# Sheet1.net
KiCad netlist of a schematic drawn in Altium Designer
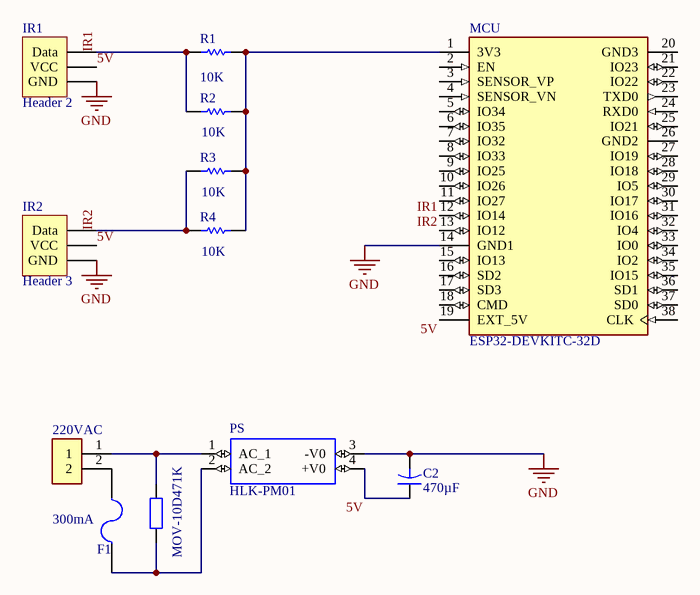
[diagram p0: Sheet1.SchDoc]

(export (version "E")
  (design (tool "Eeschema 10.0.6"))
  (components
    (comp (ref "220VAC")
      (value "282837-2")
      (footprint "TE_282837-2")
      (description "Connector Terminal Blocks Receptacle 2 Position 5.08mm Solder Straight Thru-Hole 13.5A/Contact")
      (fields (field (name "MF") "TE Connectivity") (field (name "DIGI-KEY_PART_NUMBER") "A113320-ND"))
      (libsource (lib "282837-2") (part "282837-2"))
    )
    (comp (ref "C2")
      (value "470µF")
      (footprint "CAPR5-4X5")
      (description "Capacitor")
      (fields (field (name "Comment") "Cap2") (field (name "PUBLISHER") "Altium Limited"))
      (libsource (lib "Miscellaneous Devices") (part "Cap2"))
    )
    (comp (ref "F1")
      (value "300mA")
      (footprint "PIN-W2/E2.8")
      (description "Fuse")
      (fields (field (name "PUBLISHER") "Altium Limited"))
      (libsource (lib "Miscellaneous Devices") (part "Fuse 2"))
    )
    (comp (ref "IR1")
      (value "Header 2")
      (footprint "HDR1X3")
      (description "Header, 3-Pin")
      (fields (field (name "PUBLISHER") "Altium Limited"))
      (libsource (lib "Miscellaneous Connectors") (part "Header 3"))
    )
    (comp (ref "IR2")
      (value "Header 3")
      (footprint "HDR1X3")
      (description "Header, 3-Pin")
      (fields (field (name "PUBLISHER") "Altium Limited"))
      (libsource (lib "Miscellaneous Connectors") (part "Header 3"))
    )
    (comp (ref "MCU")
      (value "ESP32-DEVKITC-32D")
      (footprint "MODULE_ESP32-DEVKITC-32D")
      (fields (field (name "MF") "Espressif Systems"))
      (libsource (lib "ESP32-DEVKITC-32D") (part "ESP32-DEVKITC-32D"))
    )
    (comp (ref "PS")
      (value "HLK-PM01")
      (footprint "HLKPM01")
      (fields (field (name "MF") "Hi-link") (field (name "MP") "hlk-pm01"))
      (libsource (lib "HLK-PM01") (part "HLK-PM01"))
    )
    (comp (ref "R1")
      (value "10K")
      (footprint "AXIAL-0.3")
      (description "Resistor")
      (fields (field (name "PUBLISHER") "Altium Limited"))
      (libsource (lib "Miscellaneous Devices") (part "Res1"))
    )
    (comp (ref "R2")
      (value "10K")
      (footprint "AXIAL-0.3")
      (description "Resistor")
      (fields (field (name "PUBLISHER") "Altium Limited"))
      (libsource (lib "Miscellaneous Devices") (part "Res1"))
    )
    (comp (ref "R3")
      (value "10K")
      (footprint "AXIAL-0.3")
      (description "Resistor")
      (fields (field (name "PUBLISHER") "Altium Limited"))
      (libsource (lib "Miscellaneous Devices") (part "Res1"))
    )
    (comp (ref "R4")
      (value "10K")
      (footprint "AXIAL-0.3")
      (description "Resistor")
      (fields (field (name "PUBLISHER") "Altium Limited"))
      (libsource (lib "Miscellaneous Devices") (part "Res1"))
    )
    (comp (ref "VAR1")
      (value "MOV-10D471K")
      (footprint "AXIAL-0.4")
      (fields (field (name "PUBLISHER") "Altium Limited"))
      (libsource (lib "Miscellaneous Devices") (part "Res2"))
    )
  )
  (nets
    (net (code "1") (name "/5V") (class "Default")
      (node (ref "C2") (pin "1") (pinfunction "1_1") (pintype "passive"))
      (node (ref "IR1") (pin "2") (pinfunction "VCC_2") (pintype "passive"))
      (node (ref "IR2") (pin "2") (pinfunction "VCC_2") (pintype "passive"))
      (node (ref "MCU") (pin "19") (pinfunction "EXT_5V_19") (pintype "power_in"))
      (node (ref "PS") (pin "4") (pinfunction "+V0_4") (pintype "bidirectional"))
    )
    (net (code "2") (name "/IR1") (class "Default")
      (node (ref "IR1") (pin "3") (pinfunction "Data_3") (pintype "passive"))
      (node (ref "MCU") (pin "12") (pinfunction "IO14_12") (pintype "bidirectional"))
      (node (ref "R1") (pin "2") (pinfunction "2_2") (pintype "passive"))
      (node (ref "R2") (pin "2") (pinfunction "2_2") (pintype "passive"))
    )
    (net (code "3") (name "/IR2") (class "Default")
      (node (ref "IR2") (pin "3") (pinfunction "Data_3") (pintype "passive"))
      (node (ref "MCU") (pin "13") (pinfunction "IO12_13") (pintype "bidirectional"))
      (node (ref "R3") (pin "2") (pinfunction "2_2") (pintype "passive"))
      (node (ref "R4") (pin "2") (pinfunction "2_2") (pintype "passive"))
    )
    (net (code "4") (name "GND") (class "Default")
      (node (ref "C2") (pin "2") (pinfunction "2_2") (pintype "passive"))
      (node (ref "IR1") (pin "1") (pinfunction "GND_1") (pintype "passive"))
      (node (ref "IR2") (pin "1") (pinfunction "GND_1") (pintype "passive"))
      (node (ref "MCU") (pin "14") (pinfunction "GND1_14") (pintype "power_in"))
      (node (ref "PS") (pin "3") (pinfunction "-V0_3") (pintype "bidirectional"))
    )
    (net (code "5") (name "Net-(220VAC-Pad2)") (class "Default")
      (node (ref "220VAC") (pin "2") (pinfunction "2_2") (pintype "passive"))
      (node (ref "F1") (pin "2") (pinfunction "2_2") (pintype "passive"))
    )
    (net (code "6") (name "Net-(MCU-3V3)") (class "Default")
      (node (ref "MCU") (pin "1") (pinfunction "3V3_1") (pintype "power_in"))
      (node (ref "R1") (pin "1") (pinfunction "1_1") (pintype "passive"))
      (node (ref "R2") (pin "1") (pinfunction "1_1") (pintype "passive"))
      (node (ref "R3") (pin "1") (pinfunction "1_1") (pintype "passive"))
      (node (ref "R4") (pin "1") (pinfunction "1_1") (pintype "passive"))
    )
    (net (code "7") (name "Net-(PS-AC_1)") (class "Default")
      (node (ref "220VAC") (pin "1") (pinfunction "1_1") (pintype "passive"))
      (node (ref "PS") (pin "1") (pinfunction "AC_1_1") (pintype "bidirectional"))
      (node (ref "VAR1") (pin "2") (pinfunction "2_2") (pintype "passive"))
    )
    (net (code "8") (name "Net-(PS-AC_2)") (class "Default")
      (node (ref "F1") (pin "1") (pinfunction "1_1") (pintype "passive"))
      (node (ref "PS") (pin "2") (pinfunction "AC_2_2") (pintype "bidirectional"))
      (node (ref "VAR1") (pin "1") (pinfunction "1_1") (pintype "passive"))
    )
    (net (code "9") (name "unconnected-(MCU-CLK-Pad38)") (class "Default")
      (node (ref "MCU") (pin "38") (pinfunction "CLK_38") (pintype "input"))
    )
    (net (code "10") (name "unconnected-(MCU-CMD-Pad18)") (class "Default")
      (node (ref "MCU") (pin "18") (pinfunction "CMD_18") (pintype "bidirectional"))
    )
    (net (code "11") (name "unconnected-(MCU-EN-Pad2)") (class "Default")
      (node (ref "MCU") (pin "2") (pinfunction "EN_2") (pintype "input"))
    )
    (net (code "12") (name "unconnected-(MCU-GND2-Pad26)") (class "Default")
      (node (ref "MCU") (pin "26") (pinfunction "GND2_26") (pintype "power_in"))
    )
    (net (code "13") (name "unconnected-(MCU-GND3-Pad20)") (class "Default")
      (node (ref "MCU") (pin "20") (pinfunction "GND3_20") (pintype "power_in"))
    )
    (net (code "14") (name "unconnected-(MCU-IO0-Pad33)") (class "Default")
      (node (ref "MCU") (pin "33") (pinfunction "IO0_33") (pintype "bidirectional"))
    )
    (net (code "15") (name "unconnected-(MCU-IO2-Pad34)") (class "Default")
      (node (ref "MCU") (pin "34") (pinfunction "IO2_34") (pintype "bidirectional"))
    )
    (net (code "16") (name "unconnected-(MCU-IO4-Pad32)") (class "Default")
      (node (ref "MCU") (pin "32") (pinfunction "IO4_32") (pintype "bidirectional"))
    )
    (net (code "17") (name "unconnected-(MCU-IO5-Pad29)") (class "Default")
      (node (ref "MCU") (pin "29") (pinfunction "IO5_29") (pintype "bidirectional"))
    )
    (net (code "18") (name "unconnected-(MCU-IO13-Pad15)") (class "Default")
      (node (ref "MCU") (pin "15") (pinfunction "IO13_15") (pintype "bidirectional"))
    )
    (net (code "19") (name "unconnected-(MCU-IO15-Pad35)") (class "Default")
      (node (ref "MCU") (pin "35") (pinfunction "IO15_35") (pintype "bidirectional"))
    )
    (net (code "20") (name "unconnected-(MCU-IO16-Pad31)") (class "Default")
      (node (ref "MCU") (pin "31") (pinfunction "IO16_31") (pintype "bidirectional"))
    )
    (net (code "21") (name "unconnected-(MCU-IO17-Pad30)") (class "Default")
      (node (ref "MCU") (pin "30") (pinfunction "IO17_30") (pintype "bidirectional"))
    )
    (net (code "22") (name "unconnected-(MCU-IO18-Pad28)") (class "Default")
      (node (ref "MCU") (pin "28") (pinfunction "IO18_28") (pintype "bidirectional"))
    )
    (net (code "23") (name "unconnected-(MCU-IO19-Pad27)") (class "Default")
      (node (ref "MCU") (pin "27") (pinfunction "IO19_27") (pintype "bidirectional"))
    )
    (net (code "24") (name "unconnected-(MCU-IO21-Pad25)") (class "Default")
      (node (ref "MCU") (pin "25") (pinfunction "IO21_25") (pintype "bidirectional"))
    )
    (net (code "25") (name "unconnected-(MCU-IO22-Pad22)") (class "Default")
      (node (ref "MCU") (pin "22") (pinfunction "IO22_22") (pintype "bidirectional"))
    )
    (net (code "26") (name "unconnected-(MCU-IO23-Pad21)") (class "Default")
      (node (ref "MCU") (pin "21") (pinfunction "IO23_21") (pintype "bidirectional"))
    )
    (net (code "27") (name "unconnected-(MCU-IO25-Pad9)") (class "Default")
      (node (ref "MCU") (pin "9") (pinfunction "IO25_9") (pintype "bidirectional"))
    )
    (net (code "28") (name "unconnected-(MCU-IO26-Pad10)") (class "Default")
      (node (ref "MCU") (pin "10") (pinfunction "IO26_10") (pintype "bidirectional"))
    )
    (net (code "29") (name "unconnected-(MCU-IO27-Pad11)") (class "Default")
      (node (ref "MCU") (pin "11") (pinfunction "IO27_11") (pintype "bidirectional"))
    )
    (net (code "30") (name "unconnected-(MCU-IO32-Pad7)") (class "Default")
      (node (ref "MCU") (pin "7") (pinfunction "IO32_7") (pintype "bidirectional"))
    )
    (net (code "31") (name "unconnected-(MCU-IO33-Pad8)") (class "Default")
      (node (ref "MCU") (pin "8") (pinfunction "IO33_8") (pintype "bidirectional"))
    )
    (net (code "32") (name "unconnected-(MCU-IO34-Pad5)") (class "Default")
      (node (ref "MCU") (pin "5") (pinfunction "IO34_5") (pintype "bidirectional"))
    )
    (net (code "33") (name "unconnected-(MCU-IO35-Pad6)") (class "Default")
      (node (ref "MCU") (pin "6") (pinfunction "IO35_6") (pintype "bidirectional"))
    )
    (net (code "34") (name "unconnected-(MCU-RXD0-Pad24)") (class "Default")
      (node (ref "MCU") (pin "24") (pinfunction "RXD0_24") (pintype "input"))
    )
    (net (code "35") (name "unconnected-(MCU-SD0-Pad37)") (class "Default")
      (node (ref "MCU") (pin "37") (pinfunction "SD0_37") (pintype "bidirectional"))
    )
    (net (code "36") (name "unconnected-(MCU-SD1-Pad36)") (class "Default")
      (node (ref "MCU") (pin "36") (pinfunction "SD1_36") (pintype "bidirectional"))
    )
    (net (code "37") (name "unconnected-(MCU-SD2-Pad16)") (class "Default")
      (node (ref "MCU") (pin "16") (pinfunction "SD2_16") (pintype "bidirectional"))
    )
    (net (code "38") (name "unconnected-(MCU-SD3-Pad17)") (class "Default")
      (node (ref "MCU") (pin "17") (pinfunction "SD3_17") (pintype "bidirectional"))
    )
    (net (code "39") (name "unconnected-(MCU-SENSOR_VN-Pad4)") (class "Default")
      (node (ref "MCU") (pin "4") (pinfunction "SENSOR_VN_4") (pintype "input"))
    )
    (net (code "40") (name "unconnected-(MCU-SENSOR_VP-Pad3)") (class "Default")
      (node (ref "MCU") (pin "3") (pinfunction "SENSOR_VP_3") (pintype "input"))
    )
    (net (code "41") (name "unconnected-(MCU-TXD0-Pad23)") (class "Default")
      (node (ref "MCU") (pin "23") (pinfunction "TXD0_23") (pintype "output"))
    )
  )
)
